# openLRSngRX32.net
KiCad netlist of a schematic drawn in EAGLE
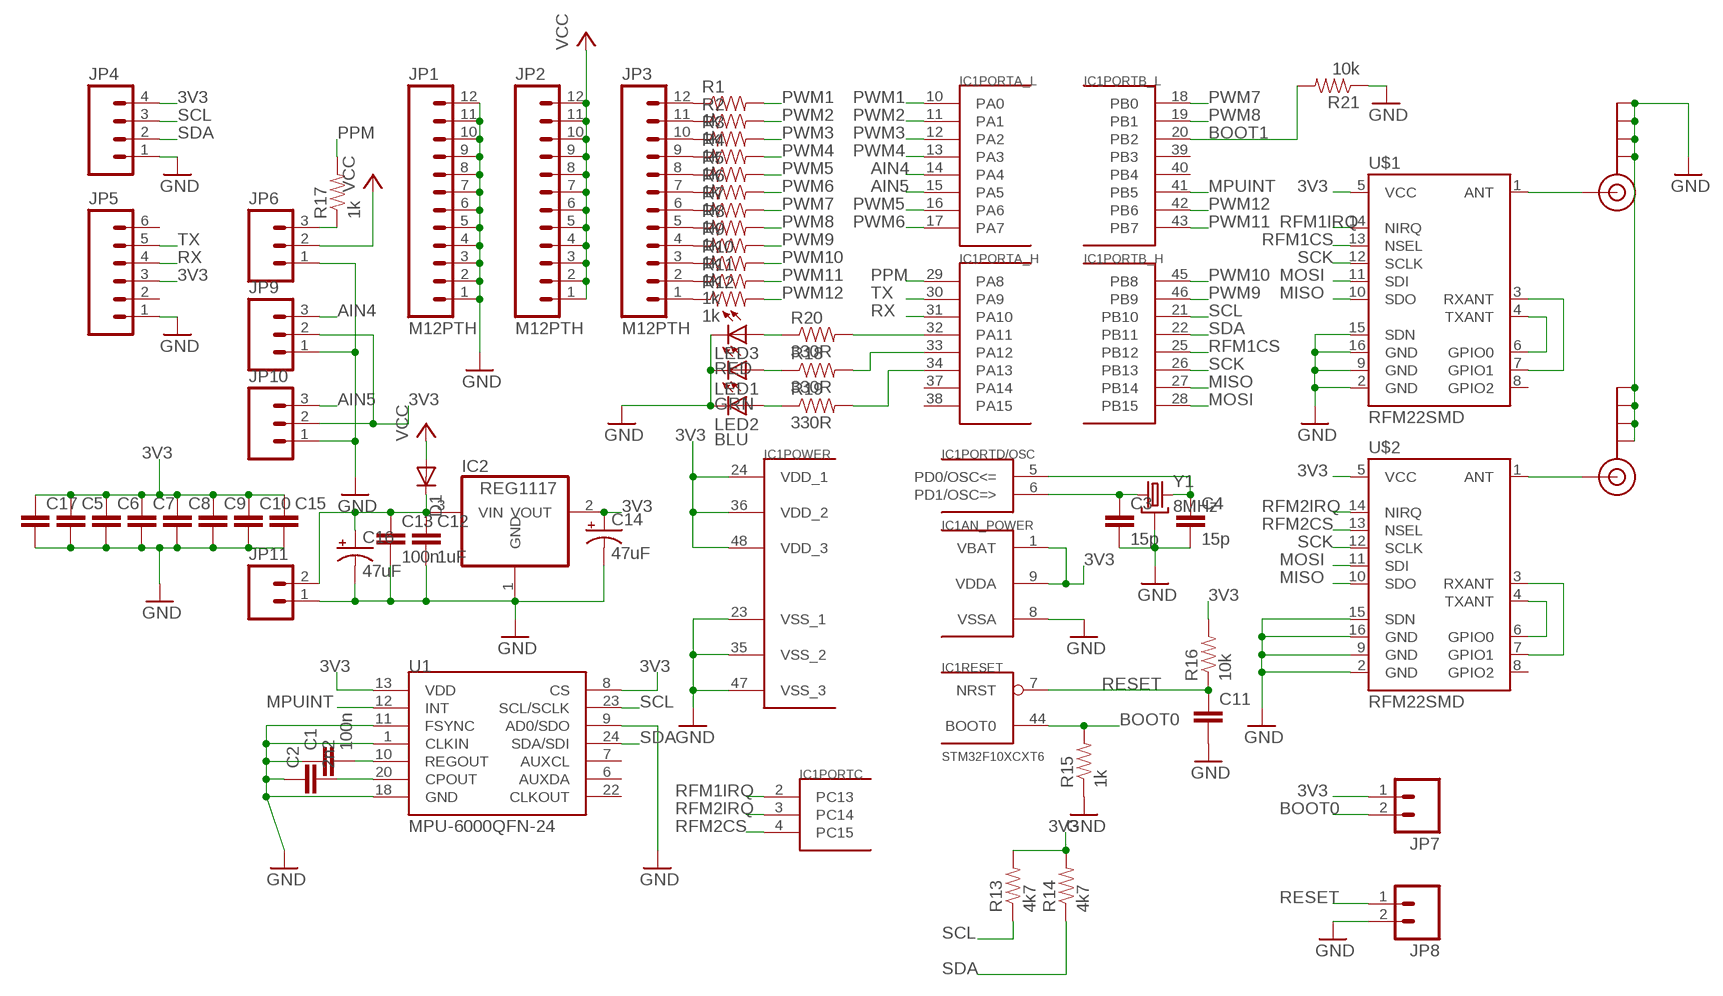
[diagram p0: schematic, sheet 1]

(export (version "E")
  (design (tool "Eeschema 10.0.6"))
  (components
    (comp (ref "C1")
      (value "100n")
      (footprint "eagle-import:0805")
      (libsource (lib "eagle-import") (part "CAP0805"))
    )
    (comp (ref "C2")
      (value "2n2")
      (footprint "eagle-import:0805")
      (libsource (lib "eagle-import") (part "CAP0805"))
    )
    (comp (ref "C3")
      (value "15p")
      (footprint "eagle-import:0805")
      (libsource (lib "eagle-import") (part "CAP0805"))
    )
    (comp (ref "C4")
      (value "15p")
      (footprint "eagle-import:0805")
      (libsource (lib "eagle-import") (part "CAP0805"))
    )
    (comp (ref "C5")
      (value "CAP0805")
      (footprint "eagle-import:0805")
      (libsource (lib "eagle-import") (part "CAP0805"))
    )
    (comp (ref "C6")
      (value "CAP0805")
      (footprint "eagle-import:0805")
      (libsource (lib "eagle-import") (part "CAP0805"))
    )
    (comp (ref "C7")
      (value "CAP0805")
      (footprint "eagle-import:0805")
      (libsource (lib "eagle-import") (part "CAP0805"))
    )
    (comp (ref "C8")
      (value "CAP0805")
      (footprint "eagle-import:0805")
      (libsource (lib "eagle-import") (part "CAP0805"))
    )
    (comp (ref "C9")
      (value "CAP0805")
      (footprint "eagle-import:0805")
      (libsource (lib "eagle-import") (part "CAP0805"))
    )
    (comp (ref "C10")
      (value "CAP0805")
      (footprint "eagle-import:0805")
      (libsource (lib "eagle-import") (part "CAP0805"))
    )
    (comp (ref "C11")
      (value "CAP0805")
      (footprint "eagle-import:0805")
      (libsource (lib "eagle-import") (part "CAP0805"))
    )
    (comp (ref "C12")
      (value "1uF")
      (footprint "eagle-import:0805")
      (libsource (lib "eagle-import") (part "CAP0805"))
    )
    (comp (ref "C13")
      (value "100n")
      (footprint "eagle-import:0805")
      (libsource (lib "eagle-import") (part "CAP0805"))
    )
    (comp (ref "C14")
      (value "47uF")
      (footprint "eagle-import:EIA3528")
      (libsource (lib "eagle-import") (part "47UF-TANT"))
    )
    (comp (ref "C15")
      (value "CAP0805")
      (footprint "eagle-import:0805")
      (libsource (lib "eagle-import") (part "CAP0805"))
    )
    (comp (ref "C16")
      (value "47uF")
      (footprint "eagle-import:EIA3528")
      (libsource (lib "eagle-import") (part "47UF-TANT"))
    )
    (comp (ref "C17")
      (value "CAP0805")
      (footprint "eagle-import:0805")
      (libsource (lib "eagle-import") (part "CAP0805"))
    )
    (comp (ref "D1")
      (value "DIODE-DO-214AC")
      (footprint "eagle-import:DO-214AC")
      (libsource (lib "eagle-import") (part "DIODE-DO-214AC"))
    )
    (comp (ref "IC1")
      (value "STM32F10XCXT6")
      (footprint "eagle-import:TQFP48")
      (libsource (lib "eagle-import") (part "STM32F10XCXT6"))
    )
    (comp (ref "IC2")
      (value "REG1117")
      (footprint "eagle-import:SOT223")
      (libsource (lib "eagle-import") (part "REG1117"))
    )
    (comp (ref "J$1")
      (value "SMA_EDGE")
      (footprint "eagle-import:SMA-EDGE")
      (libsource (lib "eagle-import") (part "SMA_EDGE"))
    )
    (comp (ref "J$2")
      (value "SMA_EDGE")
      (footprint "eagle-import:SMA-EDGE")
      (libsource (lib "eagle-import") (part "SMA_EDGE"))
    )
    (comp (ref "JP1")
      (value "M12PTH")
      (footprint "eagle-import:1X12")
      (libsource (lib "eagle-import") (part "M12PTH"))
    )
    (comp (ref "JP2")
      (value "M12PTH")
      (footprint "eagle-import:1X12")
      (libsource (lib "eagle-import") (part "M12PTH"))
    )
    (comp (ref "JP3")
      (value "M12PTH")
      (footprint "eagle-import:1X12")
      (libsource (lib "eagle-import") (part "M12PTH"))
    )
    (comp (ref "JP4")
      (value "M04PTH")
      (footprint "eagle-import:1X04")
      (libsource (lib "eagle-import") (part "M04PTH"))
    )
    (comp (ref "JP5")
      (value "M06SIP")
      (footprint "eagle-import:1X06")
      (libsource (lib "eagle-import") (part "M06SIP"))
    )
    (comp (ref "JP6")
      (value "M03PTH")
      (footprint "eagle-import:1X03")
      (libsource (lib "eagle-import") (part "M03PTH"))
    )
    (comp (ref "JP7")
      (value "M02PTH")
      (footprint "eagle-import:1X02")
      (libsource (lib "eagle-import") (part "M02PTH"))
    )
    (comp (ref "JP8")
      (value "M02PTH")
      (footprint "eagle-import:1X02")
      (libsource (lib "eagle-import") (part "M02PTH"))
    )
    (comp (ref "JP9")
      (value "M03PTH")
      (footprint "eagle-import:1X03")
      (libsource (lib "eagle-import") (part "M03PTH"))
    )
    (comp (ref "JP10")
      (value "M03PTH")
      (footprint "eagle-import:1X03")
      (libsource (lib "eagle-import") (part "M03PTH"))
    )
    (comp (ref "JP11")
      (value "M02PTH")
      (footprint "eagle-import:1X02")
      (libsource (lib "eagle-import") (part "M02PTH"))
    )
    (comp (ref "LED1")
      (value "GRN")
      (footprint "eagle-import:SML0805")
      (libsource (lib "eagle-import") (part "LEDSML0805"))
    )
    (comp (ref "LED2")
      (value "BLU")
      (footprint "eagle-import:SML0805")
      (libsource (lib "eagle-import") (part "LEDSML0805"))
    )
    (comp (ref "LED3")
      (value "RED")
      (footprint "eagle-import:SML0805")
      (libsource (lib "eagle-import") (part "LEDSML0805"))
    )
    (comp (ref "R1")
      (value "1k")
      (footprint "eagle-import:0805")
      (libsource (lib "eagle-import") (part "RESISTOR0805-RES"))
    )
    (comp (ref "R2")
      (value "1k")
      (footprint "eagle-import:0805")
      (libsource (lib "eagle-import") (part "RESISTOR0805-RES"))
    )
    (comp (ref "R3")
      (value "1k")
      (footprint "eagle-import:0805")
      (libsource (lib "eagle-import") (part "RESISTOR0805-RES"))
    )
    (comp (ref "R4")
      (value "1k")
      (footprint "eagle-import:0805")
      (libsource (lib "eagle-import") (part "RESISTOR0805-RES"))
    )
    (comp (ref "R5")
      (value "1k")
      (footprint "eagle-import:0805")
      (libsource (lib "eagle-import") (part "RESISTOR0805-RES"))
    )
    (comp (ref "R6")
      (value "1k")
      (footprint "eagle-import:0805")
      (libsource (lib "eagle-import") (part "RESISTOR0805-RES"))
    )
    (comp (ref "R7")
      (value "1k")
      (footprint "eagle-import:0805")
      (libsource (lib "eagle-import") (part "RESISTOR0805-RES"))
    )
    (comp (ref "R8")
      (value "1k")
      (footprint "eagle-import:0805")
      (libsource (lib "eagle-import") (part "RESISTOR0805-RES"))
    )
    (comp (ref "R9")
      (value "1k")
      (footprint "eagle-import:0805")
      (libsource (lib "eagle-import") (part "RESISTOR0805-RES"))
    )
    (comp (ref "R10")
      (value "1k")
      (footprint "eagle-import:0805")
      (libsource (lib "eagle-import") (part "RESISTOR0805-RES"))
    )
    (comp (ref "R11")
      (value "1k")
      (footprint "eagle-import:0805")
      (libsource (lib "eagle-import") (part "RESISTOR0805-RES"))
    )
    (comp (ref "R12")
      (value "1k")
      (footprint "eagle-import:0805")
      (libsource (lib "eagle-import") (part "RESISTOR0805-RES"))
    )
    (comp (ref "R13")
      (value "4k7")
      (footprint "eagle-import:0805")
      (libsource (lib "eagle-import") (part "RESISTOR0805-RES"))
    )
    (comp (ref "R14")
      (value "4k7")
      (footprint "eagle-import:0805")
      (libsource (lib "eagle-import") (part "RESISTOR0805-RES"))
    )
    (comp (ref "R15")
      (value "1k")
      (footprint "eagle-import:0805")
      (libsource (lib "eagle-import") (part "RESISTOR0805-RES"))
    )
    (comp (ref "R16")
      (value "10k")
      (footprint "eagle-import:0805")
      (libsource (lib "eagle-import") (part "RESISTOR0805-RES"))
    )
    (comp (ref "R17")
      (value "1k")
      (footprint "eagle-import:0805")
      (libsource (lib "eagle-import") (part "RESISTOR0805-RES"))
    )
    (comp (ref "R18")
      (value "330R")
      (footprint "eagle-import:0805")
      (libsource (lib "eagle-import") (part "RESISTOR0805-RES"))
    )
    (comp (ref "R19")
      (value "330R")
      (footprint "eagle-import:0805")
      (libsource (lib "eagle-import") (part "RESISTOR0805-RES"))
    )
    (comp (ref "R20")
      (value "330R")
      (footprint "eagle-import:0805")
      (libsource (lib "eagle-import") (part "RESISTOR0805-RES"))
    )
    (comp (ref "R21")
      (value "10k")
      (footprint "eagle-import:0805")
      (libsource (lib "eagle-import") (part "RESISTOR0805-RES"))
    )
    (comp (ref "U$1")
      (value "RFM22SMD")
      (footprint "eagle-import:RFM22-XXX-S2")
      (libsource (lib "eagle-import") (part "RFM22SMD"))
    )
    (comp (ref "U$2")
      (value "RFM22SMD")
      (footprint "eagle-import:RFM22-XXX-S2")
      (libsource (lib "eagle-import") (part "RFM22SMD"))
    )
    (comp (ref "U1")
      (value "MPU-6000QFN-24")
      (footprint "eagle-import:QFN-24-TESTING")
      (libsource (lib "eagle-import") (part "MPU-6000QFN-24"))
    )
    (comp (ref "Y1")
      (value "8MHz")
      (footprint "eagle-import:CRYSTAL-SMD-5X3")
      (libsource (lib "eagle-import") (part "CRYSTAL3.2X2.5"))
    )
  )
  (nets
    (net (code "1") (name "/3V3") (class "Default")
      (node (ref "C10") (pin "1") (pinfunction "1_1") (pintype "passive"))
      (node (ref "C14") (pin "A") (pinfunction "+_A") (pintype "passive"))
      (node (ref "C15") (pin "1") (pinfunction "1_1") (pintype "passive"))
      (node (ref "C17") (pin "1") (pinfunction "1_1") (pintype "passive"))
      (node (ref "C5") (pin "1") (pinfunction "1_1") (pintype "passive"))
      (node (ref "C6") (pin "1") (pinfunction "1_1") (pintype "passive"))
      (node (ref "C7") (pin "1") (pinfunction "1_1") (pintype "passive"))
      (node (ref "C8") (pin "1") (pinfunction "1_1") (pintype "passive"))
      (node (ref "C9") (pin "1") (pinfunction "1_1") (pintype "passive"))
      (node (ref "IC1") (pin "1") (pinfunction "VBAT_1") (pintype "power_in"))
      (node (ref "IC1") (pin "24") (pinfunction "VDD_1_24") (pintype "power_in"))
      (node (ref "IC1") (pin "36") (pinfunction "VDD_2_36") (pintype "power_in"))
      (node (ref "IC1") (pin "48") (pinfunction "VDD_3_48") (pintype "power_in"))
      (node (ref "IC1") (pin "9") (pinfunction "VDDA_9") (pintype "power_in"))
      (node (ref "IC2") (pin "2") (pinfunction "VOUT_2") (pintype "output"))
      (node (ref "JP10") (pin "2") (pinfunction "2_2") (pintype "passive"))
      (node (ref "JP4") (pin "4") (pinfunction "4_4") (pintype "passive"))
      (node (ref "JP5") (pin "3") (pinfunction "3_3") (pintype "passive"))
      (node (ref "JP7") (pin "1") (pinfunction "1_1") (pintype "passive"))
      (node (ref "JP9") (pin "2") (pinfunction "2_2") (pintype "passive"))
      (node (ref "R13") (pin "2") (pinfunction "2_2") (pintype "passive"))
      (node (ref "R14") (pin "2") (pinfunction "2_2") (pintype "passive"))
      (node (ref "R16") (pin "2") (pinfunction "2_2") (pintype "passive"))
      (node (ref "U$1") (pin "5") (pinfunction "VCC_5") (pintype "bidirectional"))
      (node (ref "U$2") (pin "5") (pinfunction "VCC_5") (pintype "bidirectional"))
      (node (ref "U1") (pin "13") (pinfunction "VDD_13") (pintype "bidirectional"))
      (node (ref "U1") (pin "8") (pinfunction "CS_8") (pintype "bidirectional"))
    )
    (net (code "2") (name "/AIN4") (class "Default")
      (node (ref "IC1") (pin "14") (pinfunction "PA4_14") (pintype "bidirectional"))
      (node (ref "JP9") (pin "3") (pinfunction "3_3") (pintype "passive"))
    )
    (net (code "3") (name "/AIN5") (class "Default")
      (node (ref "IC1") (pin "15") (pinfunction "PA5_15") (pintype "bidirectional"))
      (node (ref "JP10") (pin "3") (pinfunction "3_3") (pintype "passive"))
    )
    (net (code "4") (name "/BOOT0") (class "Default")
      (node (ref "IC1") (pin "44") (pinfunction "BOOT0_44") (pintype "input"))
      (node (ref "JP7") (pin "2") (pinfunction "2_2") (pintype "passive"))
      (node (ref "R15") (pin "2") (pinfunction "2_2") (pintype "passive"))
    )
    (net (code "5") (name "/BOOT1") (class "Default")
      (node (ref "IC1") (pin "20") (pinfunction "PB2_20") (pintype "bidirectional"))
      (node (ref "R21") (pin "2") (pinfunction "2_2") (pintype "passive"))
    )
    (net (code "6") (name "/MISO") (class "Default")
      (node (ref "IC1") (pin "27") (pinfunction "PB14_27") (pintype "bidirectional"))
      (node (ref "U$1") (pin "10") (pinfunction "SDO_10") (pintype "output"))
      (node (ref "U$2") (pin "10") (pinfunction "SDO_10") (pintype "output"))
    )
    (net (code "7") (name "/MOSI") (class "Default")
      (node (ref "IC1") (pin "28") (pinfunction "PB15_28") (pintype "bidirectional"))
      (node (ref "U$1") (pin "11") (pinfunction "SDI_11") (pintype "input"))
      (node (ref "U$2") (pin "11") (pinfunction "SDI_11") (pintype "input"))
    )
    (net (code "8") (name "/MPUINT") (class "Default")
      (node (ref "IC1") (pin "41") (pinfunction "PB5_41") (pintype "bidirectional"))
      (node (ref "U1") (pin "12") (pinfunction "INT_12") (pintype "bidirectional"))
    )
    (net (code "9") (name "/PPM") (class "Default")
      (node (ref "IC1") (pin "29") (pinfunction "PA8_29") (pintype "bidirectional"))
      (node (ref "R17") (pin "2") (pinfunction "2_2") (pintype "passive"))
    )
    (net (code "10") (name "/PWM1") (class "Default")
      (node (ref "IC1") (pin "10") (pinfunction "PA0_10") (pintype "bidirectional"))
      (node (ref "R1") (pin "2") (pinfunction "2_2") (pintype "passive"))
    )
    (net (code "11") (name "/PWM2") (class "Default")
      (node (ref "IC1") (pin "11") (pinfunction "PA1_11") (pintype "bidirectional"))
      (node (ref "R2") (pin "2") (pinfunction "2_2") (pintype "passive"))
    )
    (net (code "12") (name "/PWM3") (class "Default")
      (node (ref "IC1") (pin "12") (pinfunction "PA2_12") (pintype "bidirectional"))
      (node (ref "R3") (pin "2") (pinfunction "2_2") (pintype "passive"))
    )
    (net (code "13") (name "/PWM4") (class "Default")
      (node (ref "IC1") (pin "13") (pinfunction "PA3_13") (pintype "bidirectional"))
      (node (ref "R4") (pin "2") (pinfunction "2_2") (pintype "passive"))
    )
    (net (code "14") (name "/PWM5") (class "Default")
      (node (ref "IC1") (pin "16") (pinfunction "PA6_16") (pintype "bidirectional"))
      (node (ref "R5") (pin "2") (pinfunction "2_2") (pintype "passive"))
    )
    (net (code "15") (name "/PWM6") (class "Default")
      (node (ref "IC1") (pin "17") (pinfunction "PA7_17") (pintype "bidirectional"))
      (node (ref "R6") (pin "2") (pinfunction "2_2") (pintype "passive"))
    )
    (net (code "16") (name "/PWM7") (class "Default")
      (node (ref "IC1") (pin "18") (pinfunction "PB0_18") (pintype "bidirectional"))
      (node (ref "R7") (pin "2") (pinfunction "2_2") (pintype "passive"))
    )
    (net (code "17") (name "/PWM8") (class "Default")
      (node (ref "IC1") (pin "19") (pinfunction "PB1_19") (pintype "bidirectional"))
      (node (ref "R8") (pin "2") (pinfunction "2_2") (pintype "passive"))
    )
    (net (code "18") (name "/PWM9") (class "Default")
      (node (ref "IC1") (pin "46") (pinfunction "PB9_46") (pintype "bidirectional"))
      (node (ref "R9") (pin "2") (pinfunction "2_2") (pintype "passive"))
    )
    (net (code "19") (name "/PWM10") (class "Default")
      (node (ref "IC1") (pin "45") (pinfunction "PB8_45") (pintype "bidirectional"))
      (node (ref "R10") (pin "2") (pinfunction "2_2") (pintype "passive"))
    )
    (net (code "20") (name "/PWM11") (class "Default")
      (node (ref "IC1") (pin "43") (pinfunction "PB7_43") (pintype "bidirectional"))
      (node (ref "R11") (pin "2") (pinfunction "2_2") (pintype "passive"))
    )
    (net (code "21") (name "/PWM12") (class "Default")
      (node (ref "IC1") (pin "42") (pinfunction "PB6_42") (pintype "bidirectional"))
      (node (ref "R12") (pin "2") (pinfunction "2_2") (pintype "passive"))
    )
    (net (code "22") (name "/RESET") (class "Default")
      (node (ref "C11") (pin "1") (pinfunction "1_1") (pintype "passive"))
      (node (ref "IC1") (pin "7") (pinfunction "NRST_7") (pintype "input"))
      (node (ref "JP8") (pin "1") (pinfunction "1_1") (pintype "passive"))
      (node (ref "R16") (pin "1") (pinfunction "1_1") (pintype "passive"))
    )
    (net (code "23") (name "/RFM1CS") (class "Default")
      (node (ref "IC1") (pin "25") (pinfunction "PB12_25") (pintype "bidirectional"))
      (node (ref "U$1") (pin "13") (pinfunction "NSEL_13") (pintype "input"))
    )
    (net (code "24") (name "/RFM1IRQ") (class "Default")
      (node (ref "IC1") (pin "2") (pinfunction "PC13_2") (pintype "bidirectional"))
      (node (ref "U$1") (pin "14") (pinfunction "NIRQ_14") (pintype "output"))
    )
    (net (code "25") (name "/RFM2CS") (class "Default")
      (node (ref "IC1") (pin "4") (pinfunction "PC15_4") (pintype "bidirectional"))
      (node (ref "U$2") (pin "13") (pinfunction "NSEL_13") (pintype "input"))
    )
    (net (code "26") (name "/RFM2IRQ") (class "Default")
      (node (ref "IC1") (pin "3") (pinfunction "PC14_3") (pintype "bidirectional"))
      (node (ref "U$2") (pin "14") (pinfunction "NIRQ_14") (pintype "output"))
    )
    (net (code "27") (name "/RX") (class "Default")
      (node (ref "IC1") (pin "31") (pinfunction "PA10_31") (pintype "bidirectional"))
      (node (ref "JP5") (pin "4") (pinfunction "4_4") (pintype "passive"))
    )
    (net (code "28") (name "/SCK") (class "Default")
      (node (ref "IC1") (pin "26") (pinfunction "PB13_26") (pintype "bidirectional"))
      (node (ref "U$1") (pin "12") (pinfunction "SCLK_12") (pintype "input"))
      (node (ref "U$2") (pin "12") (pinfunction "SCLK_12") (pintype "input"))
    )
    (net (code "29") (name "/SCL") (class "Default")
      (node (ref "IC1") (pin "21") (pinfunction "PB10_21") (pintype "bidirectional"))
      (node (ref "JP4") (pin "3") (pinfunction "3_3") (pintype "passive"))
      (node (ref "R13") (pin "1") (pinfunction "1_1") (pintype "passive"))
      (node (ref "U1") (pin "23") (pinfunction "SCL/SCLK_23") (pintype "bidirectional"))
    )
    (net (code "30") (name "/SDA") (class "Default")
      (node (ref "IC1") (pin "22") (pinfunction "PB11_22") (pintype "bidirectional"))
      (node (ref "JP4") (pin "2") (pinfunction "2_2") (pintype "passive"))
      (node (ref "R14") (pin "1") (pinfunction "1_1") (pintype "passive"))
      (node (ref "U1") (pin "24") (pinfunction "SDA/SDI_24") (pintype "bidirectional"))
    )
    (net (code "31") (name "/TX") (class "Default")
      (node (ref "IC1") (pin "30") (pinfunction "PA9_30") (pintype "bidirectional"))
      (node (ref "JP5") (pin "5") (pinfunction "5_5") (pintype "passive"))
    )
    (net (code "32") (name "GND") (class "Default")
      (node (ref "C1") (pin "1") (pinfunction "1_1") (pintype "passive"))
      (node (ref "C10") (pin "2") (pinfunction "2_2") (pintype "passive"))
      (node (ref "C11") (pin "2") (pinfunction "2_2") (pintype "passive"))
      (node (ref "C12") (pin "2") (pinfunction "2_2") (pintype "passive"))
      (node (ref "C13") (pin "2") (pinfunction "2_2") (pintype "passive"))
      (node (ref "C14") (pin "C") (pinfunction "-_C") (pintype "passive"))
      (node (ref "C15") (pin "2") (pinfunction "2_2") (pintype "passive"))
      (node (ref "C16") (pin "C") (pinfunction "-_C") (pintype "passive"))
      (node (ref "C17") (pin "2") (pinfunction "2_2") (pintype "passive"))
      (node (ref "C2") (pin "1") (pinfunction "1_1") (pintype "passive"))
      (node (ref "C3") (pin "2") (pinfunction "2_2") (pintype "passive"))
      (node (ref "C4") (pin "2") (pinfunction "2_2") (pintype "passive"))
      (node (ref "C5") (pin "2") (pinfunction "2_2") (pintype "passive"))
      (node (ref "C6") (pin "2") (pinfunction "2_2") (pintype "passive"))
      (node (ref "C7") (pin "2") (pinfunction "2_2") (pintype "passive"))
      (node (ref "C8") (pin "2") (pinfunction "2_2") (pintype "passive"))
      (node (ref "C9") (pin "2") (pinfunction "2_2") (pintype "passive"))
      (node (ref "IC1") (pin "23") (pinfunction "VSS_1_23") (pintype "power_in"))
      (node (ref "IC1") (pin "35") (pinfunction "VSS_2_35") (pintype "power_in"))
      (node (ref "IC1") (pin "47") (pinfunction "VSS_3_47") (pintype "power_in"))
      (node (ref "IC1") (pin "8") (pinfunction "VSSA_8") (pintype "power_in"))
      (node (ref "IC2") (pin "1") (pinfunction "GND_1") (pintype "power_in"))
      (node (ref "J$1") (pin "GND@0") (pinfunction "GND_GND@0") (pintype "bidirectional"))
      (node (ref "J$1") (pin "GND@1") (pinfunction "GND_GND@1") (pintype "bidirectional"))
      (node (ref "J$1") (pin "GND@2") (pinfunction "GND_GND@2") (pintype "bidirectional"))
      (node (ref "J$1") (pin "GND@3") (pinfunction "GND_GND@3") (pintype "bidirectional"))
      (node (ref "J$2") (pin "GND@0") (pinfunction "GND_GND@0") (pintype "bidirectional"))
      (node (ref "J$2") (pin "GND@1") (pinfunction "GND_GND@1") (pintype "bidirectional"))
      (node (ref "J$2") (pin "GND@2") (pinfunction "GND_GND@2") (pintype "bidirectional"))
      (node (ref "J$2") (pin "GND@3") (pinfunction "GND_GND@3") (pintype "bidirectional"))
      (node (ref "JP1") (pin "1") (pinfunction "1_1") (pintype "passive"))
      (node (ref "JP1") (pin "10") (pinfunction "10_10") (pintype "passive"))
      (node (ref "JP1") (pin "11") (pinfunction "11_11") (pintype "passive"))
      (node (ref "JP1") (pin "12") (pinfunction "12_12") (pintype "passive"))
      (node (ref "JP1") (pin "2") (pinfunction "2_2") (pintype "passive"))
      (node (ref "JP1") (pin "3") (pinfunction "3_3") (pintype "passive"))
      (node (ref "JP1") (pin "4") (pinfunction "4_4") (pintype "passive"))
      (node (ref "JP1") (pin "5") (pinfunction "5_5") (pintype "passive"))
      (node (ref "JP1") (pin "6") (pinfunction "6_6") (pintype "passive"))
      (node (ref "JP1") (pin "7") (pinfunction "7_7") (pintype "passive"))
      (node (ref "JP1") (pin "8") (pinfunction "8_8") (pintype "passive"))
      (node (ref "JP1") (pin "9") (pinfunction "9_9") (pintype "passive"))
      (node (ref "JP10") (pin "1") (pinfunction "1_1") (pintype "passive"))
      (node (ref "JP11") (pin "1") (pinfunction "1_1") (pintype "passive"))
      (node (ref "JP4") (pin "1") (pinfunction "1_1") (pintype "passive"))
      (node (ref "JP5") (pin "1") (pinfunction "1_1") (pintype "passive"))
      (node (ref "JP6") (pin "1") (pinfunction "1_1") (pintype "passive"))
      (node (ref "JP8") (pin "2") (pinfunction "2_2") (pintype "passive"))
      (node (ref "JP9") (pin "1") (pinfunction "1_1") (pintype "passive"))
      (node (ref "LED1") (pin "C") (pinfunction "C_C") (pintype "passive"))
      (node (ref "LED2") (pin "C") (pinfunction "C_C") (pintype "passive"))
      (node (ref "LED3") (pin "C") (pinfunction "C_C") (pintype "passive"))
      (node (ref "R15") (pin "1") (pinfunction "1_1") (pintype "passive"))
      (node (ref "R21") (pin "1") (pinfunction "1_1") (pintype "passive"))
      (node (ref "U$1") (pin "15") (pinfunction "SDN_15") (pintype "input"))
      (node (ref "U$1") (pin "16") (pinfunction "GND_16") (pintype "power_in"))
      (node (ref "U$1") (pin "2") (pinfunction "GND_2") (pintype "power_in"))
      (node (ref "U$1") (pin "9") (pinfunction "GND_9") (pintype "power_in"))
      (node (ref "U$2") (pin "15") (pinfunction "SDN_15") (pintype "input"))
      (node (ref "U$2") (pin "16") (pinfunction "GND_16") (pintype "power_in"))
      (node (ref "U$2") (pin "2") (pinfunction "GND_2") (pintype "power_in"))
      (node (ref "U$2") (pin "9") (pinfunction "GND_9") (pintype "power_in"))
      (node (ref "U1") (pin "1") (pinfunction "CLKIN_1") (pintype "bidirectional"))
      (node (ref "U1") (pin "11") (pinfunction "FSYNC_11") (pintype "bidirectional"))
      (node (ref "U1") (pin "18") (pinfunction "GND_18") (pintype "bidirectional"))
      (node (ref "U1") (pin "9") (pinfunction "AD0/SDO_9") (pintype "bidirectional"))
      (node (ref "Y1") (pin "2") (pinfunction "GND_2") (pintype "power_in"))
      (node (ref "Y1") (pin "4") (pinfunction "GND_4") (pintype "power_in"))
    )
    (net (code "33") (name "Net-(C16-+)") (class "Default")
      (node (ref "C12") (pin "1") (pinfunction "1_1") (pintype "passive"))
      (node (ref "C13") (pin "1") (pinfunction "1_1") (pintype "passive"))
      (node (ref "C16") (pin "A") (pinfunction "+_A") (pintype "passive"))
      (node (ref "D1") (pin "C") (pinfunction "C_C") (pintype "passive"))
      (node (ref "IC2") (pin "3") (pinfunction "VIN_3") (pintype "input"))
      (node (ref "JP11") (pin "2") (pinfunction "2_2") (pintype "passive"))
    )
    (net (code "34") (name "Net-(IC1B-PA11)") (class "Default")
      (node (ref "IC1") (pin "32") (pinfunction "PA11_32") (pintype "bidirectional"))
      (node (ref "R20") (pin "2") (pinfunction "2_2") (pintype "passive"))
    )
    (net (code "35") (name "Net-(IC1B-PA12)") (class "Default")
      (node (ref "IC1") (pin "33") (pinfunction "PA12_33") (pintype "bidirectional"))
      (node (ref "R18") (pin "2") (pinfunction "2_2") (pintype "passive"))
    )
    (net (code "36") (name "Net-(IC1B-PA13)") (class "Default")
      (node (ref "IC1") (pin "34") (pinfunction "PA13_34") (pintype "bidirectional"))
      (node (ref "R19") (pin "2") (pinfunction "2_2") (pintype "passive"))
    )
    (net (code "37") (name "Net-(IC1G-PD0{slash}OSC<=)") (class "Default")
      (node (ref "C4") (pin "1") (pinfunction "1_1") (pintype "passive"))
      (node (ref "IC1") (pin "5") (pinfunction "PD0/OSC<=_5") (pintype "bidirectional"))
      (node (ref "Y1") (pin "3") (pinfunction "2_3") (pintype "passive"))
    )
    (net (code "38") (name "Net-(IC1G-PD1{slash}OSC=>)") (class "Default")
      (node (ref "C3") (pin "1") (pinfunction "1_1") (pintype "passive"))
      (node (ref "IC1") (pin "6") (pinfunction "PD1/OSC=>_6") (pintype "bidirectional"))
      (node (ref "Y1") (pin "1") (pinfunction "1_1") (pintype "passive"))
    )
    (net (code "39") (name "Net-(J$1-SIGNAL)") (class "Default")
      (node (ref "J$1") (pin "SIG") (pinfunction "SIGNAL_SIG") (pintype "bidirectional"))
      (node (ref "U$1") (pin "1") (pinfunction "ANT_1") (pintype "bidirectional"))
    )
    (net (code "40") (name "Net-(J$2-SIGNAL)") (class "Default")
      (node (ref "J$2") (pin "SIG") (pinfunction "SIGNAL_SIG") (pintype "bidirectional"))
      (node (ref "U$2") (pin "1") (pinfunction "ANT_1") (pintype "bidirectional"))
    )
    (net (code "41") (name "Net-(JP3-Pad1)") (class "Default")
      (node (ref "JP3") (pin "1") (pinfunction "1_1") (pintype "passive"))
      (node (ref "R12") (pin "1") (pinfunction "1_1") (pintype "passive"))
    )
    (net (code "42") (name "Net-(JP3-Pad2)") (class "Default")
      (node (ref "JP3") (pin "2") (pinfunction "2_2") (pintype "passive"))
      (node (ref "R11") (pin "1") (pinfunction "1_1") (pintype "passive"))
    )
    (net (code "43") (name "Net-(JP3-Pad3)") (class "Default")
      (node (ref "JP3") (pin "3") (pinfunction "3_3") (pintype "passive"))
      (node (ref "R10") (pin "1") (pinfunction "1_1") (pintype "passive"))
    )
    (net (code "44") (name "Net-(JP3-Pad4)") (class "Default")
      (node (ref "JP3") (pin "4") (pinfunction "4_4") (pintype "passive"))
      (node (ref "R9") (pin "1") (pinfunction "1_1") (pintype "passive"))
    )
    (net (code "45") (name "Net-(JP3-Pad5)") (class "Default")
      (node (ref "JP3") (pin "5") (pinfunction "5_5") (pintype "passive"))
      (node (ref "R8") (pin "1") (pinfunction "1_1") (pintype "passive"))
    )
    (net (code "46") (name "Net-(JP3-Pad6)") (class "Default")
      (node (ref "JP3") (pin "6") (pinfunction "6_6") (pintype "passive"))
      (node (ref "R7") (pin "1") (pinfunction "1_1") (pintype "passive"))
    )
    (net (code "47") (name "Net-(JP3-Pad7)") (class "Default")
      (node (ref "JP3") (pin "7") (pinfunction "7_7") (pintype "passive"))
      (node (ref "R6") (pin "1") (pinfunction "1_1") (pintype "passive"))
    )
    (net (code "48") (name "Net-(JP3-Pad8)") (class "Default")
      (node (ref "JP3") (pin "8") (pinfunction "8_8") (pintype "passive"))
      (node (ref "R5") (pin "1") (pinfunction "1_1") (pintype "passive"))
    )
    (net (code "49") (name "Net-(JP3-Pad9)") (class "Default")
      (node (ref "JP3") (pin "9") (pinfunction "9_9") (pintype "passive"))
      (node (ref "R4") (pin "1") (pinfunction "1_1") (pintype "passive"))
    )
    (net (code "50") (name "Net-(JP3-Pad10)") (class "Default")
      (node (ref "JP3") (pin "10") (pinfunction "10_10") (pintype "passive"))
      (node (ref "R3") (pin "1") (pinfunction "1_1") (pintype "passive"))
    )
    (net (code "51") (name "Net-(JP3-Pad11)") (class "Default")
      (node (ref "JP3") (pin "11") (pinfunction "11_11") (pintype "passive"))
      (node (ref "R2") (pin "1") (pinfunction "1_1") (pintype "passive"))
    )
    (net (code "52") (name "Net-(JP3-Pad12)") (class "Default")
      (node (ref "JP3") (pin "12") (pinfunction "12_12") (pintype "passive"))
      (node (ref "R1") (pin "1") (pinfunction "1_1") (pintype "passive"))
    )
    (net (code "53") (name "Net-(JP6-Pad3)") (class "Default")
      (node (ref "JP6") (pin "3") (pinfunction "3_3") (pintype "passive"))
      (node (ref "R17") (pin "1") (pinfunction "1_1") (pintype "passive"))
    )
    (net (code "54") (name "Net-(LED1-PadA)") (class "Default")
      (node (ref "LED1") (pin "A") (pinfunction "A_A") (pintype "passive"))
      (node (ref "R18") (pin "1") (pinfunction "1_1") (pintype "passive"))
    )
    (net (code "55") (name "Net-(LED2-PadA)") (class "Default")
      (node (ref "LED2") (pin "A") (pinfunction "A_A") (pintype "passive"))
      (node (ref "R19") (pin "1") (pinfunction "1_1") (pintype "passive"))
    )
    (net (code "56") (name "Net-(LED3-PadA)") (class "Default")
      (node (ref "LED3") (pin "A") (pinfunction "A_A") (pintype "passive"))
      (node (ref "R20") (pin "1") (pinfunction "1_1") (pintype "passive"))
    )
    (net (code "57") (name "Net-(U$1-GPIO0)") (class "Default")
      (node (ref "U$1") (pin "4") (pinfunction "TXANT_4") (pintype "input"))
      (node (ref "U$1") (pin "6") (pinfunction "GPIO0_6") (pintype "bidirectional"))
    )
    (net (code "58") (name "Net-(U$1-GPIO1)") (class "Default")
      (node (ref "U$1") (pin "3") (pinfunction "RXANT_3") (pintype "input"))
      (node (ref "U$1") (pin "7") (pinfunction "GPIO1_7") (pintype "bidirectional"))
    )
    (net (code "59") (name "Net-(U$2-GPIO0)") (class "Default")
      (node (ref "U$2") (pin "4") (pinfunction "TXANT_4") (pintype "input"))
      (node (ref "U$2") (pin "6") (pinfunction "GPIO0_6") (pintype "bidirectional"))
    )
    (net (code "60") (name "Net-(U$2-GPIO1)") (class "Default")
      (node (ref "U$2") (pin "3") (pinfunction "RXANT_3") (pintype "input"))
      (node (ref "U$2") (pin "7") (pinfunction "GPIO1_7") (pintype "bidirectional"))
    )
    (net (code "61") (name "Net-(U1-CPOUT)") (class "Default")
      (node (ref "C2") (pin "2") (pinfunction "2_2") (pintype "passive"))
      (node (ref "U1") (pin "20") (pinfunction "CPOUT_20") (pintype "bidirectional"))
    )
    (net (code "62") (name "Net-(U1-REGOUT)") (class "Default")
      (node (ref "C1") (pin "2") (pinfunction "2_2") (pintype "passive"))
      (node (ref "U1") (pin "10") (pinfunction "REGOUT_10") (pintype "bidirectional"))
    )
    (net (code "63") (name "VCC") (class "Default")
      (node (ref "D1") (pin "A") (pinfunction "A_A") (pintype "passive"))
      (node (ref "JP2") (pin "1") (pinfunction "1_1") (pintype "passive"))
      (node (ref "JP2") (pin "10") (pinfunction "10_10") (pintype "passive"))
      (node (ref "JP2") (pin "11") (pinfunction "11_11") (pintype "passive"))
      (node (ref "JP2") (pin "12") (pinfunction "12_12") (pintype "passive"))
      (node (ref "JP2") (pin "2") (pinfunction "2_2") (pintype "passive"))
      (node (ref "JP2") (pin "3") (pinfunction "3_3") (pintype "passive"))
      (node (ref "JP2") (pin "4") (pinfunction "4_4") (pintype "passive"))
      (node (ref "JP2") (pin "5") (pinfunction "5_5") (pintype "passive"))
      (node (ref "JP2") (pin "6") (pinfunction "6_6") (pintype "passive"))
      (node (ref "JP2") (pin "7") (pinfunction "7_7") (pintype "passive"))
      (node (ref "JP2") (pin "8") (pinfunction "8_8") (pintype "passive"))
      (node (ref "JP2") (pin "9") (pinfunction "9_9") (pintype "passive"))
      (node (ref "JP6") (pin "2") (pinfunction "2_2") (pintype "passive"))
    )
    (net (code "64") (name "unconnected-(IC1B-PA14-Pad37)") (class "Default")
      (node (ref "IC1") (pin "37") (pinfunction "PA14_37") (pintype "bidirectional"))
    )
    (net (code "65") (name "unconnected-(IC1B-PA15-Pad38)") (class "Default")
      (node (ref "IC1") (pin "38") (pinfunction "PA15_38") (pintype "bidirectional"))
    )
    (net (code "66") (name "unconnected-(IC1E-PB3-Pad39)") (class "Default")
      (node (ref "IC1") (pin "39") (pinfunction "PB3_39") (pintype "bidirectional"))
    )
    (net (code "67") (name "unconnected-(IC1E-PB4-Pad40)") (class "Default")
      (node (ref "IC1") (pin "40") (pinfunction "PB4_40") (pintype "bidirectional"))
    )
    (net (code "68") (name "unconnected-(JP5-Pad2)") (class "Default")
      (node (ref "JP5") (pin "2") (pinfunction "2_2") (pintype "passive"))
    )
    (net (code "69") (name "unconnected-(JP5-Pad6)") (class "Default")
      (node (ref "JP5") (pin "6") (pinfunction "6_6") (pintype "passive"))
    )
    (net (code "70") (name "unconnected-(U$1-GPIO2-Pad8)") (class "Default")
      (node (ref "U$1") (pin "8") (pinfunction "GPIO2_8") (pintype "bidirectional"))
    )
    (net (code "71") (name "unconnected-(U$2-GPIO2-Pad8)") (class "Default")
      (node (ref "U$2") (pin "8") (pinfunction "GPIO2_8") (pintype "bidirectional"))
    )
    (net (code "72") (name "unconnected-(U1-AUXCL-Pad7)") (class "Default")
      (node (ref "U1") (pin "7") (pinfunction "AUXCL_7") (pintype "bidirectional"))
    )
    (net (code "73") (name "unconnected-(U1-AUXDA-Pad6)") (class "Default")
      (node (ref "U1") (pin "6") (pinfunction "AUXDA_6") (pintype "bidirectional"))
    )
    (net (code "74") (name "unconnected-(U1-CLKOUT-Pad22)") (class "Default")
      (node (ref "U1") (pin "22") (pinfunction "CLKOUT_22") (pintype "bidirectional"))
    )
  )
)
